# HoneyPI_Platine_TimerBoard_2_00a.net
KiCad netlist of a schematic drawn in EAGLE
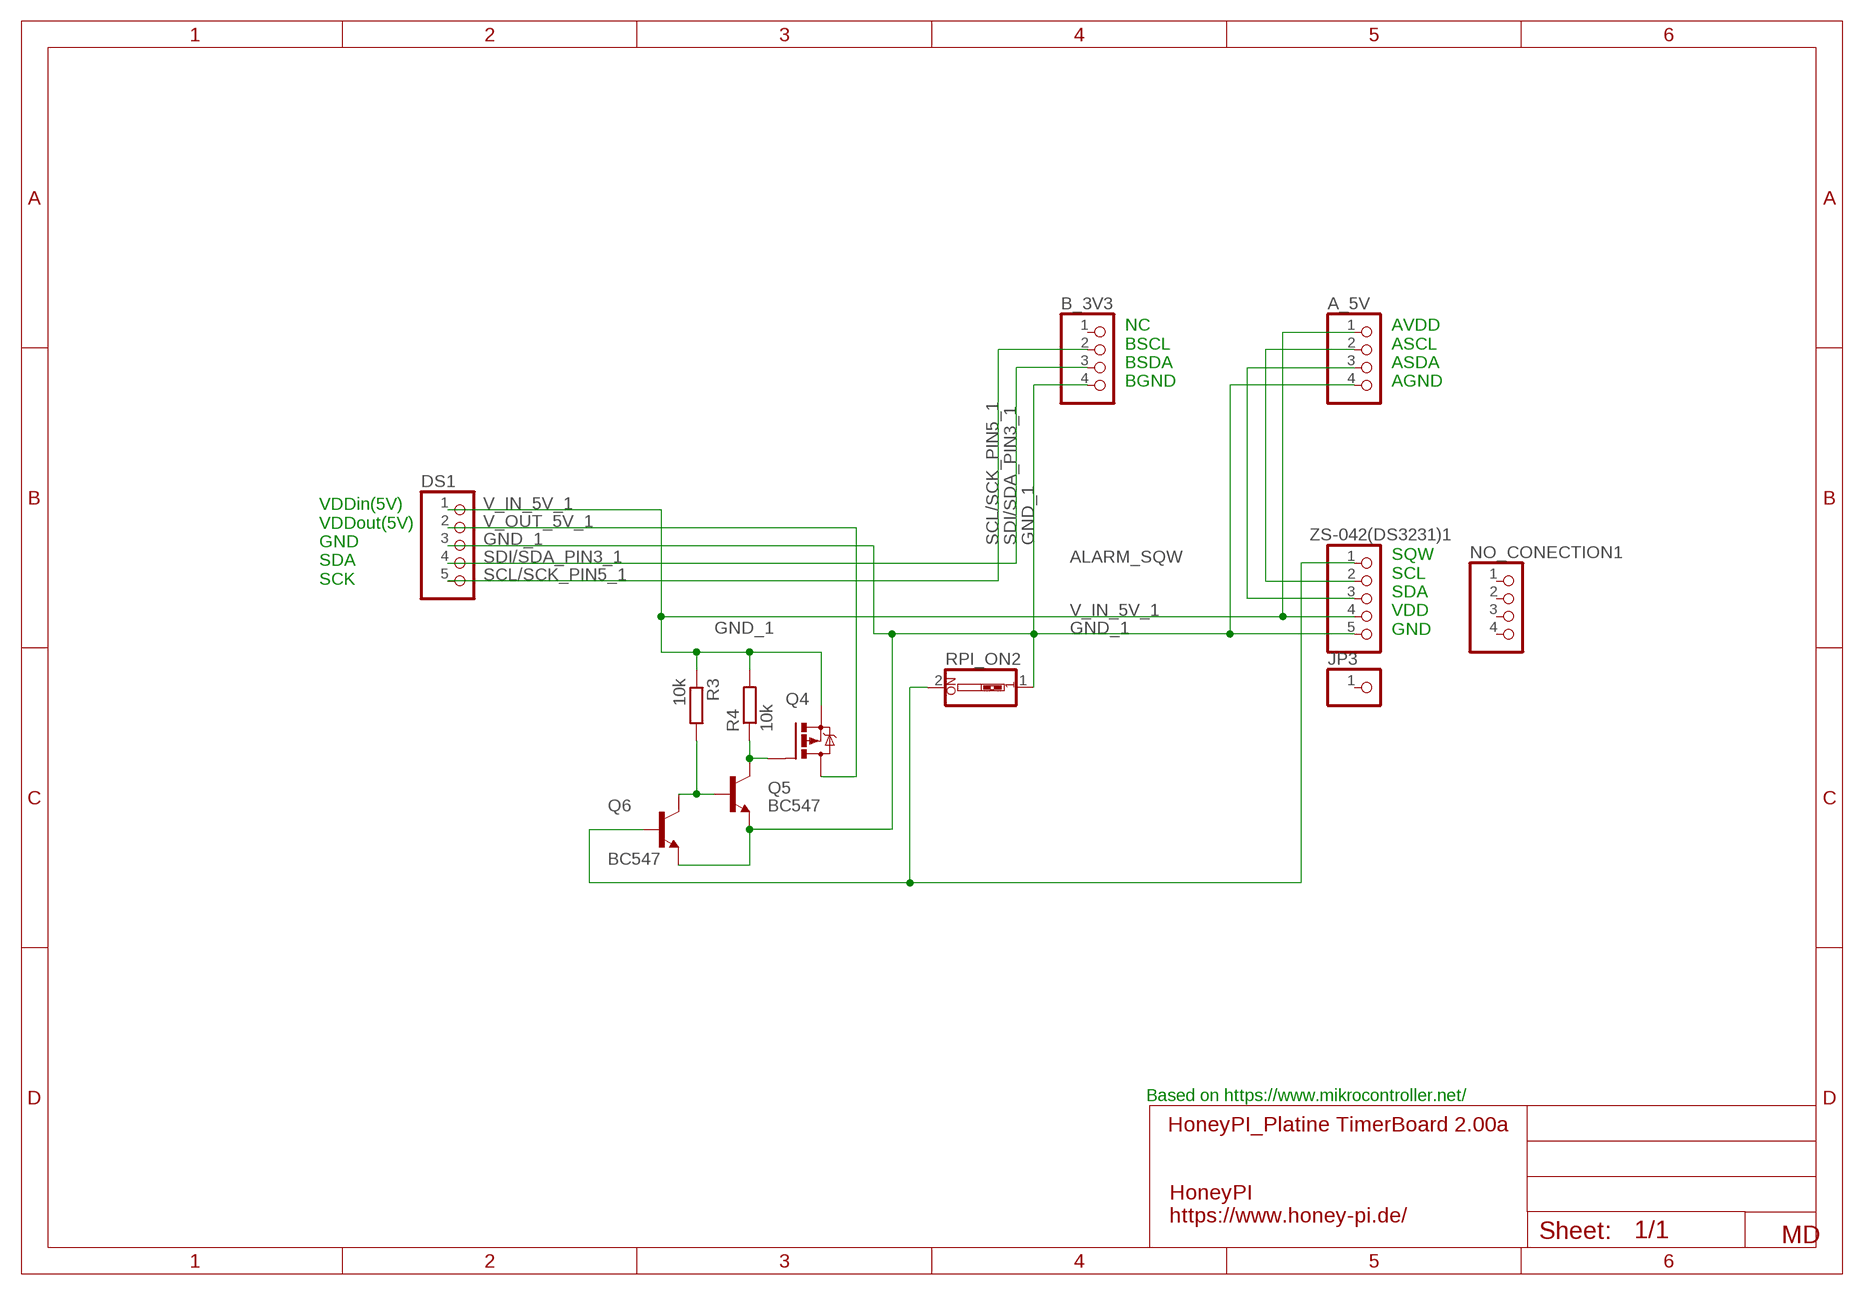
[diagram p0: schematic, sheet 1]

(export (version "E")
  (design (tool "Eeschema 10.0.6"))
  (components
    (comp (ref "A_5V")
      (value "PINHD-1X4")
      (footprint "eagle-import:1X04")
      (libsource (lib "eagle-import") (part "PINHD-1X4"))
    )
    (comp (ref "B_3V3")
      (value "PINHD-1X4")
      (footprint "eagle-import:1X04")
      (libsource (lib "eagle-import") (part "PINHD-1X4"))
    )
    (comp (ref "DS1")
      (value "PINHD-1X5")
      (footprint "eagle-import:1X05")
      (libsource (lib "eagle-import") (part "PINHD-1X5"))
    )
    (comp (ref "JP3")
      (value "PINHD-1X1")
      (footprint "eagle-import:1X01")
      (libsource (lib "eagle-import") (part "PINHD-1X1"))
    )
    (comp (ref "NO_CONECTION1")
      (value "PINHD-1X4")
      (footprint "eagle-import:1X04")
      (libsource (lib "eagle-import") (part "PINHD-1X4"))
    )
    (comp (ref "Q4")
      (value "NDP6020P")
      (footprint "eagle-import:TO220BV")
      (libsource (lib "eagle-import") (part "IRF9530"))
    )
    (comp (ref "Q5")
      (value "BC547")
      (footprint "eagle-import:TO92-EBC")
      (libsource (lib "eagle-import") (part "BC338"))
    )
    (comp (ref "Q6")
      (value "BC547")
      (footprint "eagle-import:TO92-EBC")
      (libsource (lib "eagle-import") (part "BC338"))
    )
    (comp (ref "R3")
      (value "10k")
      (footprint "eagle-import:0204_7")
      (libsource (lib "eagle-import") (part "R-EU_0204/7"))
    )
    (comp (ref "R4")
      (value "10k")
      (footprint "eagle-import:0204_7")
      (libsource (lib "eagle-import") (part "R-EU_0204/7"))
    )
    (comp (ref "RPI_ON2")
      (value "SW_DIP-1")
      (footprint "eagle-import:EDG-01")
      (libsource (lib "eagle-import") (part "SW_DIP-1"))
    )
    (comp (ref "ZS-042(DS3231)1")
      (value "PINHD-1X5")
      (footprint "eagle-import:1X05")
      (libsource (lib "eagle-import") (part "PINHD-1X5"))
    )
  )
  (nets
    (net (code "1") (name "/ALARM_SQW") (class "Default")
      (node (ref "Q6") (pin "B") (pinfunction "B_B") (pintype "passive"))
      (node (ref "RPI_ON2") (pin "2") (pinfunction "2_2") (pintype "passive"))
      (node (ref "ZS-042(DS3231)1") (pin "1") (pinfunction "1_1") (pintype "passive"))
    )
    (net (code "2") (name "/GND_1") (class "Default")
      (node (ref "A_5V") (pin "4") (pinfunction "4_4") (pintype "passive"))
      (node (ref "B_3V3") (pin "4") (pinfunction "4_4") (pintype "passive"))
      (node (ref "DS1") (pin "3") (pinfunction "3_3") (pintype "passive"))
      (node (ref "Q5") (pin "E") (pinfunction "E_E") (pintype "passive"))
      (node (ref "Q6") (pin "E") (pinfunction "E_E") (pintype "passive"))
      (node (ref "RPI_ON2") (pin "1") (pinfunction "1_1") (pintype "passive"))
      (node (ref "ZS-042(DS3231)1") (pin "5") (pinfunction "5_5") (pintype "passive"))
    )
    (net (code "3") (name "/SCL{slash}SCK_PIN5_1") (class "Default")
      (node (ref "B_3V3") (pin "2") (pinfunction "2_2") (pintype "passive"))
      (node (ref "DS1") (pin "5") (pinfunction "5_5") (pintype "passive"))
    )
    (net (code "4") (name "/SDI{slash}SDA_PIN3_1") (class "Default")
      (node (ref "B_3V3") (pin "3") (pinfunction "3_3") (pintype "passive"))
      (node (ref "DS1") (pin "4") (pinfunction "4_4") (pintype "passive"))
    )
    (net (code "5") (name "/V_IN_5V_1") (class "Default")
      (node (ref "A_5V") (pin "1") (pinfunction "1_1") (pintype "passive"))
      (node (ref "DS1") (pin "1") (pinfunction "1_1") (pintype "passive"))
      (node (ref "Q4") (pin "S") (pinfunction "S_S") (pintype "passive"))
      (node (ref "R3") (pin "1") (pinfunction "1_1") (pintype "passive"))
      (node (ref "R4") (pin "2") (pinfunction "2_2") (pintype "passive"))
      (node (ref "ZS-042(DS3231)1") (pin "4") (pinfunction "4_4") (pintype "passive"))
    )
    (net (code "6") (name "/V_OUT_5V_1") (class "Default")
      (node (ref "DS1") (pin "2") (pinfunction "2_2") (pintype "passive"))
      (node (ref "Q4") (pin "D") (pinfunction "D_D") (pintype "passive"))
    )
    (net (code "7") (name "Net-(A_5V-Pad2)") (class "Default")
      (node (ref "A_5V") (pin "2") (pinfunction "2_2") (pintype "passive"))
      (node (ref "ZS-042(DS3231)1") (pin "2") (pinfunction "2_2") (pintype "passive"))
    )
    (net (code "8") (name "Net-(A_5V-Pad3)") (class "Default")
      (node (ref "A_5V") (pin "3") (pinfunction "3_3") (pintype "passive"))
      (node (ref "ZS-042(DS3231)1") (pin "3") (pinfunction "3_3") (pintype "passive"))
    )
    (net (code "9") (name "Net-(Q4-PadG)") (class "Default")
      (node (ref "Q4") (pin "G") (pinfunction "G_G") (pintype "passive"))
      (node (ref "Q5") (pin "C") (pinfunction "C_C") (pintype "passive"))
      (node (ref "R4") (pin "1") (pinfunction "1_1") (pintype "passive"))
    )
    (net (code "10") (name "Net-(Q5-PadB)") (class "Default")
      (node (ref "Q5") (pin "B") (pinfunction "B_B") (pintype "passive"))
      (node (ref "Q6") (pin "C") (pinfunction "C_C") (pintype "passive"))
      (node (ref "R3") (pin "2") (pinfunction "2_2") (pintype "passive"))
    )
    (net (code "11") (name "unconnected-(B_3V3-Pad1)") (class "Default")
      (node (ref "B_3V3") (pin "1") (pinfunction "1_1") (pintype "passive"))
    )
    (net (code "12") (name "unconnected-(JP3-Pad1)") (class "Default")
      (node (ref "JP3") (pin "1") (pinfunction "1_1") (pintype "passive"))
    )
    (net (code "13") (name "unconnected-(NO_CONECTION1-Pad1)") (class "Default")
      (node (ref "NO_CONECTION1") (pin "1") (pinfunction "1_1") (pintype "passive"))
    )
    (net (code "14") (name "unconnected-(NO_CONECTION1-Pad2)") (class "Default")
      (node (ref "NO_CONECTION1") (pin "2") (pinfunction "2_2") (pintype "passive"))
    )
    (net (code "15") (name "unconnected-(NO_CONECTION1-Pad3)") (class "Default")
      (node (ref "NO_CONECTION1") (pin "3") (pinfunction "3_3") (pintype "passive"))
    )
    (net (code "16") (name "unconnected-(NO_CONECTION1-Pad4)") (class "Default")
      (node (ref "NO_CONECTION1") (pin "4") (pinfunction "4_4") (pintype "passive"))
    )
  )
)
